# LQFP-64_to_breadboard.net
KiCad netlist of a schematic drawn in EAGLE
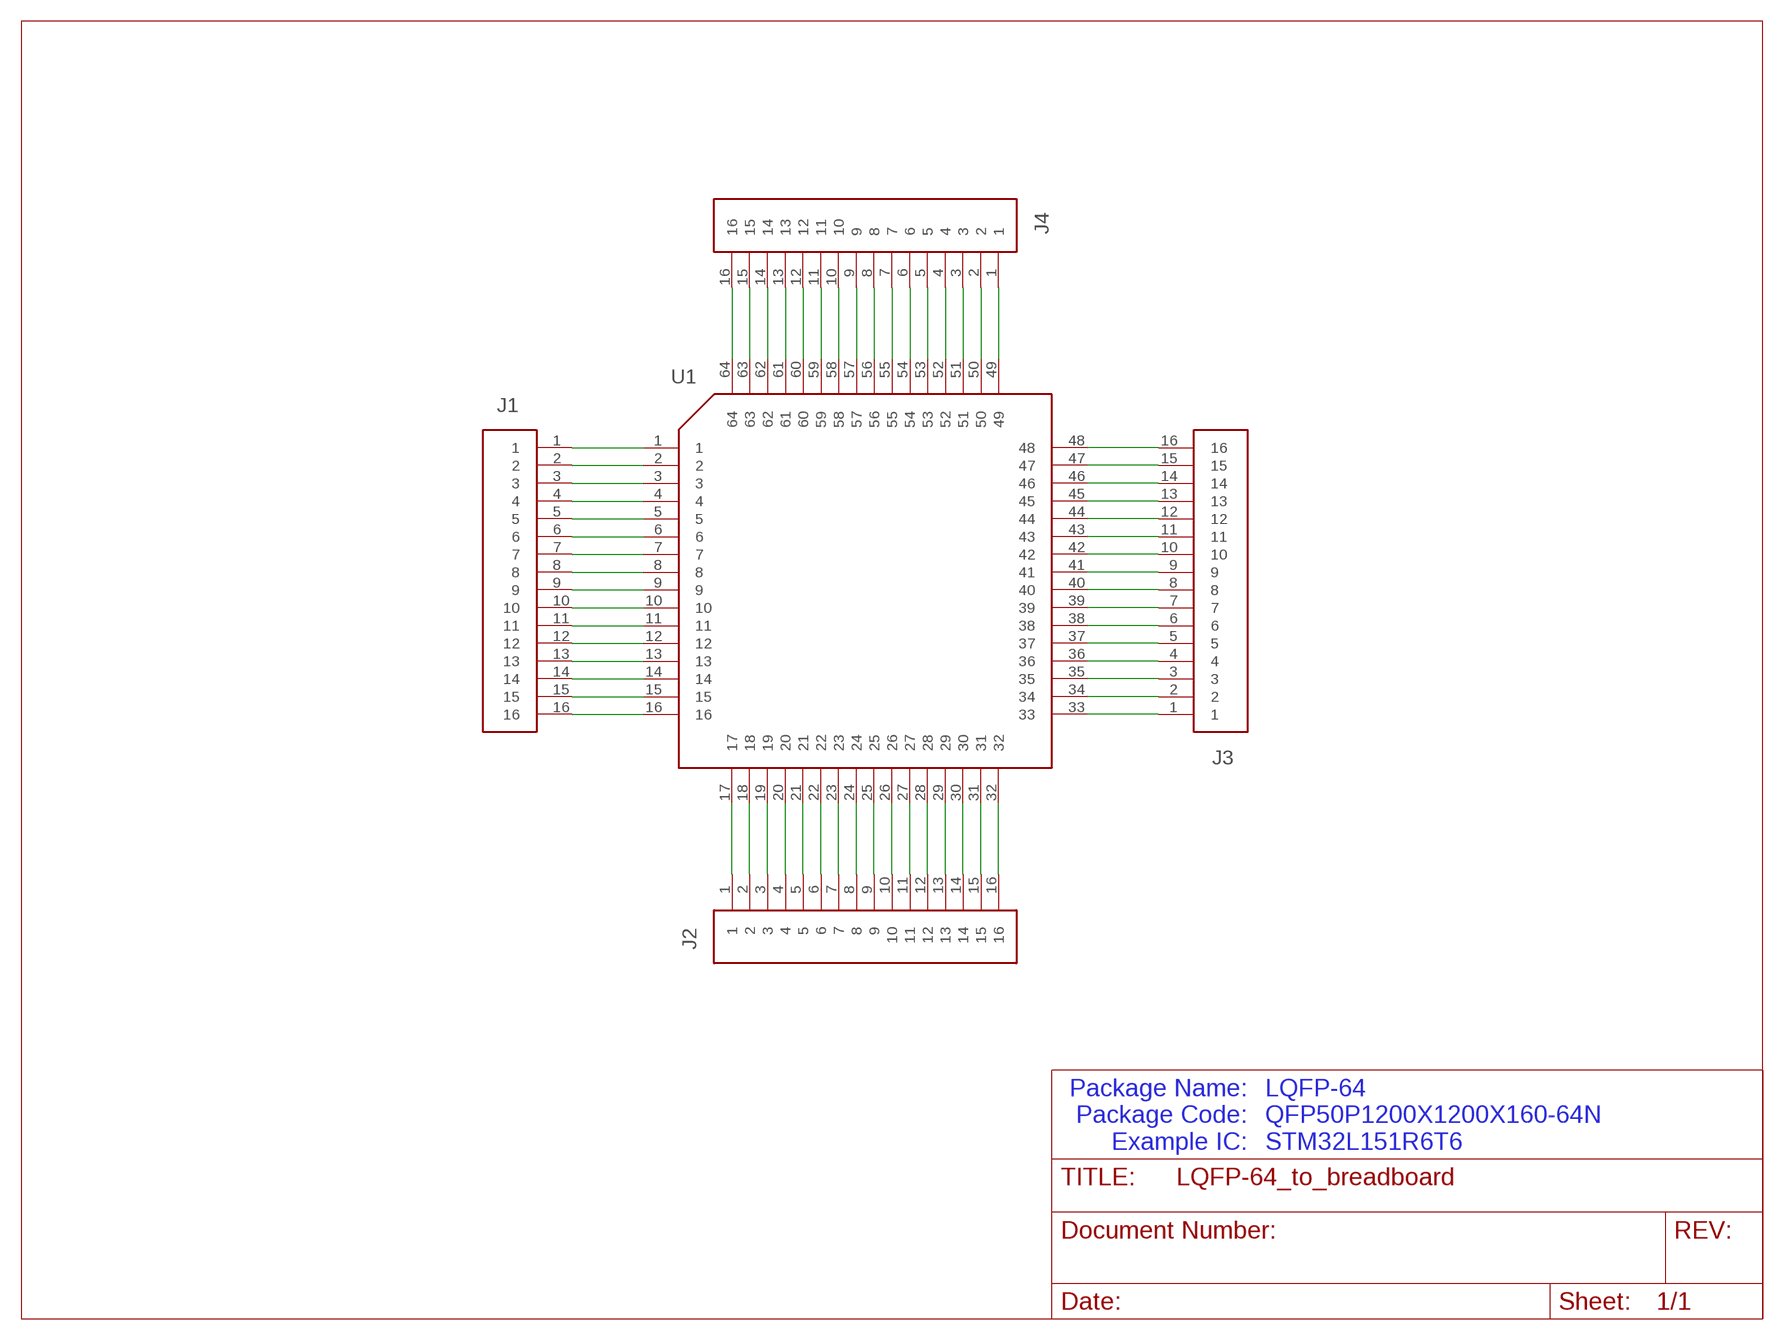
[diagram p0: schematic, sheet 1]

(export (version "E")
  (design (tool "Eeschema 10.0.6"))
  (components
    (comp (ref "J1")
      (value "CONNECTOR_16")
      (footprint "eagle-import:68000-116HLF")
      (libsource (lib "eagle-import") (part "CONNECTOR_16"))
    )
    (comp (ref "J2")
      (value "CONNECTOR_16-NO_SQUARE")
      (footprint "eagle-import:68000-116HLF-NO-SQUARE")
      (libsource (lib "eagle-import") (part "CONNECTOR_16-NO_SQUARE"))
    )
    (comp (ref "J3")
      (value "CONNECTOR_16-NO_SQUARE")
      (footprint "eagle-import:68000-116HLF-NO-SQUARE")
      (libsource (lib "eagle-import") (part "CONNECTOR_16-NO_SQUARE"))
    )
    (comp (ref "J4")
      (value "CONNECTOR_16-NO_SQUARE")
      (footprint "eagle-import:68000-116HLF-NO-SQUARE")
      (libsource (lib "eagle-import") (part "CONNECTOR_16-NO_SQUARE"))
    )
    (comp (ref "U1")
      (value "IC_GENERIC_64-LQFP")
      (footprint "eagle-import:QFP50P1200X1200X160-64N")
      (libsource (lib "eagle-import") (part "IC_GENERIC_64-LQFP"))
    )
  )
  (nets
    (net (code "1") (name "Net-(J1-Pad1)") (class "Default")
      (node (ref "J1") (pin "1") (pinfunction "1_1") (pintype "bidirectional"))
      (node (ref "U1") (pin "1") (pinfunction "1_1") (pintype "bidirectional"))
    )
    (net (code "2") (name "Net-(J1-Pad2)") (class "Default")
      (node (ref "J1") (pin "2") (pinfunction "2_2") (pintype "bidirectional"))
      (node (ref "U1") (pin "2") (pinfunction "2_2") (pintype "bidirectional"))
    )
    (net (code "3") (name "Net-(J1-Pad3)") (class "Default")
      (node (ref "J1") (pin "3") (pinfunction "3_3") (pintype "bidirectional"))
      (node (ref "U1") (pin "3") (pinfunction "3_3") (pintype "bidirectional"))
    )
    (net (code "4") (name "Net-(J1-Pad4)") (class "Default")
      (node (ref "J1") (pin "4") (pinfunction "4_4") (pintype "bidirectional"))
      (node (ref "U1") (pin "4") (pinfunction "4_4") (pintype "bidirectional"))
    )
    (net (code "5") (name "Net-(J1-Pad5)") (class "Default")
      (node (ref "J1") (pin "5") (pinfunction "5_5") (pintype "bidirectional"))
      (node (ref "U1") (pin "5") (pinfunction "5_5") (pintype "bidirectional"))
    )
    (net (code "6") (name "Net-(J1-Pad6)") (class "Default")
      (node (ref "J1") (pin "6") (pinfunction "6_6") (pintype "bidirectional"))
      (node (ref "U1") (pin "6") (pinfunction "6_6") (pintype "bidirectional"))
    )
    (net (code "7") (name "Net-(J1-Pad7)") (class "Default")
      (node (ref "J1") (pin "7") (pinfunction "7_7") (pintype "bidirectional"))
      (node (ref "U1") (pin "7") (pinfunction "7_7") (pintype "bidirectional"))
    )
    (net (code "8") (name "Net-(J1-Pad8)") (class "Default")
      (node (ref "J1") (pin "8") (pinfunction "8_8") (pintype "bidirectional"))
      (node (ref "U1") (pin "8") (pinfunction "8_8") (pintype "bidirectional"))
    )
    (net (code "9") (name "Net-(J1-Pad9)") (class "Default")
      (node (ref "J1") (pin "9") (pinfunction "9_9") (pintype "bidirectional"))
      (node (ref "U1") (pin "9") (pinfunction "9_9") (pintype "bidirectional"))
    )
    (net (code "10") (name "Net-(J1-Pad10)") (class "Default")
      (node (ref "J1") (pin "10") (pinfunction "10_10") (pintype "bidirectional"))
      (node (ref "U1") (pin "10") (pinfunction "10_10") (pintype "bidirectional"))
    )
    (net (code "11") (name "Net-(J1-Pad11)") (class "Default")
      (node (ref "J1") (pin "11") (pinfunction "11_11") (pintype "bidirectional"))
      (node (ref "U1") (pin "11") (pinfunction "11_11") (pintype "bidirectional"))
    )
    (net (code "12") (name "Net-(J1-Pad12)") (class "Default")
      (node (ref "J1") (pin "12") (pinfunction "12_12") (pintype "bidirectional"))
      (node (ref "U1") (pin "12") (pinfunction "12_12") (pintype "bidirectional"))
    )
    (net (code "13") (name "Net-(J1-Pad13)") (class "Default")
      (node (ref "J1") (pin "13") (pinfunction "13_13") (pintype "bidirectional"))
      (node (ref "U1") (pin "13") (pinfunction "13_13") (pintype "bidirectional"))
    )
    (net (code "14") (name "Net-(J1-Pad14)") (class "Default")
      (node (ref "J1") (pin "14") (pinfunction "14_14") (pintype "bidirectional"))
      (node (ref "U1") (pin "14") (pinfunction "14_14") (pintype "bidirectional"))
    )
    (net (code "15") (name "Net-(J1-Pad15)") (class "Default")
      (node (ref "J1") (pin "15") (pinfunction "15_15") (pintype "bidirectional"))
      (node (ref "U1") (pin "15") (pinfunction "15_15") (pintype "bidirectional"))
    )
    (net (code "16") (name "Net-(J1-Pad16)") (class "Default")
      (node (ref "J1") (pin "16") (pinfunction "16_16") (pintype "bidirectional"))
      (node (ref "U1") (pin "16") (pinfunction "16_16") (pintype "bidirectional"))
    )
    (net (code "17") (name "Net-(J2-Pad1)") (class "Default")
      (node (ref "J2") (pin "1") (pinfunction "1_1") (pintype "bidirectional"))
      (node (ref "U1") (pin "17") (pinfunction "17_17") (pintype "bidirectional"))
    )
    (net (code "18") (name "Net-(J2-Pad2)") (class "Default")
      (node (ref "J2") (pin "2") (pinfunction "2_2") (pintype "bidirectional"))
      (node (ref "U1") (pin "18") (pinfunction "18_18") (pintype "bidirectional"))
    )
    (net (code "19") (name "Net-(J2-Pad3)") (class "Default")
      (node (ref "J2") (pin "3") (pinfunction "3_3") (pintype "bidirectional"))
      (node (ref "U1") (pin "19") (pinfunction "19_19") (pintype "bidirectional"))
    )
    (net (code "20") (name "Net-(J2-Pad4)") (class "Default")
      (node (ref "J2") (pin "4") (pinfunction "4_4") (pintype "bidirectional"))
      (node (ref "U1") (pin "20") (pinfunction "20_20") (pintype "bidirectional"))
    )
    (net (code "21") (name "Net-(J2-Pad5)") (class "Default")
      (node (ref "J2") (pin "5") (pinfunction "5_5") (pintype "bidirectional"))
      (node (ref "U1") (pin "21") (pinfunction "21_21") (pintype "bidirectional"))
    )
    (net (code "22") (name "Net-(J2-Pad6)") (class "Default")
      (node (ref "J2") (pin "6") (pinfunction "6_6") (pintype "bidirectional"))
      (node (ref "U1") (pin "22") (pinfunction "22_22") (pintype "bidirectional"))
    )
    (net (code "23") (name "Net-(J2-Pad7)") (class "Default")
      (node (ref "J2") (pin "7") (pinfunction "7_7") (pintype "bidirectional"))
      (node (ref "U1") (pin "23") (pinfunction "23_23") (pintype "bidirectional"))
    )
    (net (code "24") (name "Net-(J2-Pad8)") (class "Default")
      (node (ref "J2") (pin "8") (pinfunction "8_8") (pintype "bidirectional"))
      (node (ref "U1") (pin "24") (pinfunction "24_24") (pintype "bidirectional"))
    )
    (net (code "25") (name "Net-(J2-Pad9)") (class "Default")
      (node (ref "J2") (pin "9") (pinfunction "9_9") (pintype "bidirectional"))
      (node (ref "U1") (pin "25") (pinfunction "25_25") (pintype "bidirectional"))
    )
    (net (code "26") (name "Net-(J2-Pad10)") (class "Default")
      (node (ref "J2") (pin "10") (pinfunction "10_10") (pintype "bidirectional"))
      (node (ref "U1") (pin "26") (pinfunction "26_26") (pintype "bidirectional"))
    )
    (net (code "27") (name "Net-(J2-Pad11)") (class "Default")
      (node (ref "J2") (pin "11") (pinfunction "11_11") (pintype "bidirectional"))
      (node (ref "U1") (pin "27") (pinfunction "27_27") (pintype "bidirectional"))
    )
    (net (code "28") (name "Net-(J2-Pad12)") (class "Default")
      (node (ref "J2") (pin "12") (pinfunction "12_12") (pintype "bidirectional"))
      (node (ref "U1") (pin "28") (pinfunction "28_28") (pintype "bidirectional"))
    )
    (net (code "29") (name "Net-(J2-Pad13)") (class "Default")
      (node (ref "J2") (pin "13") (pinfunction "13_13") (pintype "bidirectional"))
      (node (ref "U1") (pin "29") (pinfunction "29_29") (pintype "bidirectional"))
    )
    (net (code "30") (name "Net-(J2-Pad14)") (class "Default")
      (node (ref "J2") (pin "14") (pinfunction "14_14") (pintype "bidirectional"))
      (node (ref "U1") (pin "30") (pinfunction "30_30") (pintype "bidirectional"))
    )
    (net (code "31") (name "Net-(J2-Pad15)") (class "Default")
      (node (ref "J2") (pin "15") (pinfunction "15_15") (pintype "bidirectional"))
      (node (ref "U1") (pin "31") (pinfunction "31_31") (pintype "bidirectional"))
    )
    (net (code "32") (name "Net-(J2-Pad16)") (class "Default")
      (node (ref "J2") (pin "16") (pinfunction "16_16") (pintype "bidirectional"))
      (node (ref "U1") (pin "32") (pinfunction "32_32") (pintype "bidirectional"))
    )
    (net (code "33") (name "Net-(J3-Pad1)") (class "Default")
      (node (ref "J3") (pin "1") (pinfunction "1_1") (pintype "bidirectional"))
      (node (ref "U1") (pin "33") (pinfunction "33_33") (pintype "bidirectional"))
    )
    (net (code "34") (name "Net-(J3-Pad2)") (class "Default")
      (node (ref "J3") (pin "2") (pinfunction "2_2") (pintype "bidirectional"))
      (node (ref "U1") (pin "34") (pinfunction "34_34") (pintype "bidirectional"))
    )
    (net (code "35") (name "Net-(J3-Pad3)") (class "Default")
      (node (ref "J3") (pin "3") (pinfunction "3_3") (pintype "bidirectional"))
      (node (ref "U1") (pin "35") (pinfunction "35_35") (pintype "bidirectional"))
    )
    (net (code "36") (name "Net-(J3-Pad4)") (class "Default")
      (node (ref "J3") (pin "4") (pinfunction "4_4") (pintype "bidirectional"))
      (node (ref "U1") (pin "36") (pinfunction "36_36") (pintype "bidirectional"))
    )
    (net (code "37") (name "Net-(J3-Pad5)") (class "Default")
      (node (ref "J3") (pin "5") (pinfunction "5_5") (pintype "bidirectional"))
      (node (ref "U1") (pin "37") (pinfunction "37_37") (pintype "bidirectional"))
    )
    (net (code "38") (name "Net-(J3-Pad6)") (class "Default")
      (node (ref "J3") (pin "6") (pinfunction "6_6") (pintype "bidirectional"))
      (node (ref "U1") (pin "38") (pinfunction "38_38") (pintype "bidirectional"))
    )
    (net (code "39") (name "Net-(J3-Pad7)") (class "Default")
      (node (ref "J3") (pin "7") (pinfunction "7_7") (pintype "bidirectional"))
      (node (ref "U1") (pin "39") (pinfunction "39_39") (pintype "bidirectional"))
    )
    (net (code "40") (name "Net-(J3-Pad8)") (class "Default")
      (node (ref "J3") (pin "8") (pinfunction "8_8") (pintype "bidirectional"))
      (node (ref "U1") (pin "40") (pinfunction "40_40") (pintype "bidirectional"))
    )
    (net (code "41") (name "Net-(J3-Pad9)") (class "Default")
      (node (ref "J3") (pin "9") (pinfunction "9_9") (pintype "bidirectional"))
      (node (ref "U1") (pin "41") (pinfunction "41_41") (pintype "bidirectional"))
    )
    (net (code "42") (name "Net-(J3-Pad10)") (class "Default")
      (node (ref "J3") (pin "10") (pinfunction "10_10") (pintype "bidirectional"))
      (node (ref "U1") (pin "42") (pinfunction "42_42") (pintype "bidirectional"))
    )
    (net (code "43") (name "Net-(J3-Pad11)") (class "Default")
      (node (ref "J3") (pin "11") (pinfunction "11_11") (pintype "bidirectional"))
      (node (ref "U1") (pin "43") (pinfunction "43_43") (pintype "bidirectional"))
    )
    (net (code "44") (name "Net-(J3-Pad12)") (class "Default")
      (node (ref "J3") (pin "12") (pinfunction "12_12") (pintype "bidirectional"))
      (node (ref "U1") (pin "44") (pinfunction "44_44") (pintype "bidirectional"))
    )
    (net (code "45") (name "Net-(J3-Pad13)") (class "Default")
      (node (ref "J3") (pin "13") (pinfunction "13_13") (pintype "bidirectional"))
      (node (ref "U1") (pin "45") (pinfunction "45_45") (pintype "bidirectional"))
    )
    (net (code "46") (name "Net-(J3-Pad14)") (class "Default")
      (node (ref "J3") (pin "14") (pinfunction "14_14") (pintype "bidirectional"))
      (node (ref "U1") (pin "46") (pinfunction "46_46") (pintype "bidirectional"))
    )
    (net (code "47") (name "Net-(J3-Pad15)") (class "Default")
      (node (ref "J3") (pin "15") (pinfunction "15_15") (pintype "bidirectional"))
      (node (ref "U1") (pin "47") (pinfunction "47_47") (pintype "bidirectional"))
    )
    (net (code "48") (name "Net-(J3-Pad16)") (class "Default")
      (node (ref "J3") (pin "16") (pinfunction "16_16") (pintype "bidirectional"))
      (node (ref "U1") (pin "48") (pinfunction "48_48") (pintype "bidirectional"))
    )
    (net (code "49") (name "Net-(J4-Pad1)") (class "Default")
      (node (ref "J4") (pin "1") (pinfunction "1_1") (pintype "bidirectional"))
      (node (ref "U1") (pin "49") (pinfunction "49_49") (pintype "bidirectional"))
    )
    (net (code "50") (name "Net-(J4-Pad2)") (class "Default")
      (node (ref "J4") (pin "2") (pinfunction "2_2") (pintype "bidirectional"))
      (node (ref "U1") (pin "50") (pinfunction "50_50") (pintype "bidirectional"))
    )
    (net (code "51") (name "Net-(J4-Pad3)") (class "Default")
      (node (ref "J4") (pin "3") (pinfunction "3_3") (pintype "bidirectional"))
      (node (ref "U1") (pin "51") (pinfunction "51_51") (pintype "bidirectional"))
    )
    (net (code "52") (name "Net-(J4-Pad4)") (class "Default")
      (node (ref "J4") (pin "4") (pinfunction "4_4") (pintype "bidirectional"))
      (node (ref "U1") (pin "52") (pinfunction "52_52") (pintype "bidirectional"))
    )
    (net (code "53") (name "Net-(J4-Pad5)") (class "Default")
      (node (ref "J4") (pin "5") (pinfunction "5_5") (pintype "bidirectional"))
      (node (ref "U1") (pin "53") (pinfunction "53_53") (pintype "bidirectional"))
    )
    (net (code "54") (name "Net-(J4-Pad6)") (class "Default")
      (node (ref "J4") (pin "6") (pinfunction "6_6") (pintype "bidirectional"))
      (node (ref "U1") (pin "54") (pinfunction "54_54") (pintype "bidirectional"))
    )
    (net (code "55") (name "Net-(J4-Pad7)") (class "Default")
      (node (ref "J4") (pin "7") (pinfunction "7_7") (pintype "bidirectional"))
      (node (ref "U1") (pin "55") (pinfunction "55_55") (pintype "bidirectional"))
    )
    (net (code "56") (name "Net-(J4-Pad8)") (class "Default")
      (node (ref "J4") (pin "8") (pinfunction "8_8") (pintype "bidirectional"))
      (node (ref "U1") (pin "56") (pinfunction "56_56") (pintype "bidirectional"))
    )
    (net (code "57") (name "Net-(J4-Pad9)") (class "Default")
      (node (ref "J4") (pin "9") (pinfunction "9_9") (pintype "bidirectional"))
      (node (ref "U1") (pin "57") (pinfunction "57_57") (pintype "bidirectional"))
    )
    (net (code "58") (name "Net-(J4-Pad10)") (class "Default")
      (node (ref "J4") (pin "10") (pinfunction "10_10") (pintype "bidirectional"))
      (node (ref "U1") (pin "58") (pinfunction "58_58") (pintype "bidirectional"))
    )
    (net (code "59") (name "Net-(J4-Pad11)") (class "Default")
      (node (ref "J4") (pin "11") (pinfunction "11_11") (pintype "bidirectional"))
      (node (ref "U1") (pin "59") (pinfunction "59_59") (pintype "bidirectional"))
    )
    (net (code "60") (name "Net-(J4-Pad12)") (class "Default")
      (node (ref "J4") (pin "12") (pinfunction "12_12") (pintype "bidirectional"))
      (node (ref "U1") (pin "60") (pinfunction "60_60") (pintype "bidirectional"))
    )
    (net (code "61") (name "Net-(J4-Pad13)") (class "Default")
      (node (ref "J4") (pin "13") (pinfunction "13_13") (pintype "bidirectional"))
      (node (ref "U1") (pin "61") (pinfunction "61_61") (pintype "bidirectional"))
    )
    (net (code "62") (name "Net-(J4-Pad14)") (class "Default")
      (node (ref "J4") (pin "14") (pinfunction "14_14") (pintype "bidirectional"))
      (node (ref "U1") (pin "62") (pinfunction "62_62") (pintype "bidirectional"))
    )
    (net (code "63") (name "Net-(J4-Pad15)") (class "Default")
      (node (ref "J4") (pin "15") (pinfunction "15_15") (pintype "bidirectional"))
      (node (ref "U1") (pin "63") (pinfunction "63_63") (pintype "bidirectional"))
    )
    (net (code "64") (name "Net-(J4-Pad16)") (class "Default")
      (node (ref "J4") (pin "16") (pinfunction "16_16") (pintype "bidirectional"))
      (node (ref "U1") (pin "64") (pinfunction "64_64") (pintype "bidirectional"))
    )
  )
)
